# Kit_Rele_v1_SCH.net
KiCad netlist of a schematic drawn in Altium Designer
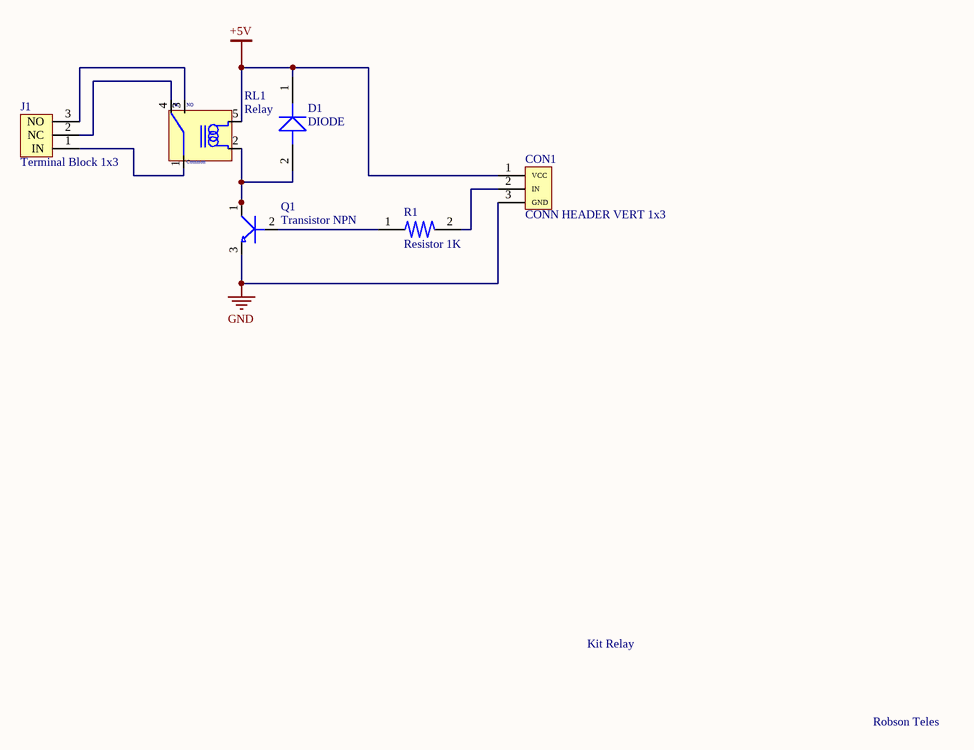
[diagram p0: Kit_Rele_v1_SCH.SchDoc]

(export (version "E")
  (design (tool "Eeschema 10.0.6"))
  (components
    (comp (ref "CON1")
      (value "CONN HEADER VERT 1x3")
      (footprint "CONN HEADER")
      (description "Board-To-Board Connector, Vertical, Wr-Phd Series, Through Hole, Header, 3, 2.54 Mm")
      (fields
        (field (name "MANUFACTURER") "Wurth Electronics")
        (field (name "MANUFACTURER PART NUMBER") "61300311121")
      )
      (libsource (lib "Kit_Rele_v1_SCHLib") (part "61300311121"))
    )
    (comp (ref "D1")
      (value "DIODE")
      (footprint "DIODE BAT54")
      (description "Small Signal Schottky Diode, Single, 30 V, 200 mA, 800 mV, 600 mA, 150 C ;RoHS Compliant: Yes")
      (fields
        (field (name "MANUFACTURER") "ON Semiconductor / Fairchild")
        (field (name "MANUFACTURER PART NUMBER") "BAT54HT1G")
      )
      (libsource (lib "Kit_Rele_v1_SCHLib") (part "BAT54HT1G"))
    )
    (comp (ref "J1")
      (value "Terminal Block 1x3")
      (footprint "Terminal Block")
      (fields
        (field (name "MANUFACTURER") "Phoenix Contact")
        (field (name "MANUFACTURER PART NUMBER") "1935174")
        (field (name "VOLTAGE") "300V")
      )
      (libsource (lib "Kit_Rele_v1_SCHLib") (part "1935174"))
    )
    (comp (ref "Q1")
      (value "Transistor NPN")
      (footprint "Transistor SOT-23")
      (description "TRANS NPN 40V 0.2A SOT23")
      (fields (field (name "MANUFACTURER") "MCC") (field (name "MANUFACTURER PART NUMBER") "MMBT3904-TP"))
      (libsource (lib "Kit_Rele_v1_SCHLib") (part "MMBT3904-TP"))
    )
    (comp (ref "R1")
      (value "Resistor 1K")
      (footprint "R1206")
      (description "RES SMD 1K OHM 5% 1/4W 1206")
      (fields
        (field (name "MANUFACTURER") "Yageo")
        (field (name "MANUFACTURER PART NUMBER") "RC1206JR-071KL")
      )
      (libsource (lib "Kit_Rele_v1_SCHLib") (part "RC1206JR-071KL"))
    )
    (comp (ref "RL1")
      (value "Relay")
      (footprint "Relay")
      (description "RELAY GEN PURPOSE SPDT 10A 5V")
      (fields (field (name "MANUFACTURER") "Omron") (field (name "MANUFACTURER PART NUMBER") "G5LE-1-36DC5"))
      (libsource (lib "Kit_Rele_v1_SCHLib") (part "G5LE-1-36DC5"))
    )
  )
  (nets
    (net (code "1") (name "+5V") (class "Default")
      (node (ref "CON1") (pin "1") (pinfunction "VCC_1") (pintype "passive"))
      (node (ref "D1") (pin "1") (pinfunction "1_1") (pintype "passive"))
      (node (ref "RL1") (pin "5") (pinfunction "5_5") (pintype "passive"))
    )
    (net (code "2") (name "GND") (class "Default")
      (node (ref "CON1") (pin "3") (pinfunction "GND_3") (pintype "passive"))
      (node (ref "Q1") (pin "3") (pinfunction "3_3") (pintype "passive"))
    )
    (net (code "3") (name "Net-(CON1-IN)") (class "Default")
      (node (ref "CON1") (pin "2") (pinfunction "IN_2") (pintype "passive"))
      (node (ref "R1") (pin "2") (pinfunction "2_2") (pintype "passive"))
    )
    (net (code "4") (name "Net-(D1-Pad2)") (class "Default")
      (node (ref "D1") (pin "2") (pinfunction "2_2") (pintype "passive"))
      (node (ref "Q1") (pin "1") (pinfunction "1_1") (pintype "passive"))
      (node (ref "RL1") (pin "2") (pinfunction "2_2") (pintype "passive"))
    )
    (net (code "5") (name "Net-(J1-IN)") (class "Default")
      (node (ref "J1") (pin "1") (pinfunction "IN_1") (pintype "passive"))
      (node (ref "RL1") (pin "1") (pinfunction "1_1") (pintype "passive"))
    )
    (net (code "6") (name "Net-(J1-NC)") (class "Default")
      (node (ref "J1") (pin "2") (pinfunction "NC_2") (pintype "passive"))
      (node (ref "RL1") (pin "4") (pinfunction "4_4") (pintype "passive"))
    )
    (net (code "7") (name "Net-(J1-NO)") (class "Default")
      (node (ref "J1") (pin "3") (pinfunction "NO_3") (pintype "passive"))
      (node (ref "RL1") (pin "3") (pinfunction "3_3") (pintype "passive"))
    )
    (net (code "8") (name "Net-(Q1-Pad2)") (class "Default")
      (node (ref "Q1") (pin "2") (pinfunction "2_2") (pintype "passive"))
      (node (ref "R1") (pin "1") (pinfunction "1_1") (pintype "passive"))
    )
  )
)
